# Colour_Sensor.net
KiCad netlist of a schematic drawn in EAGLE
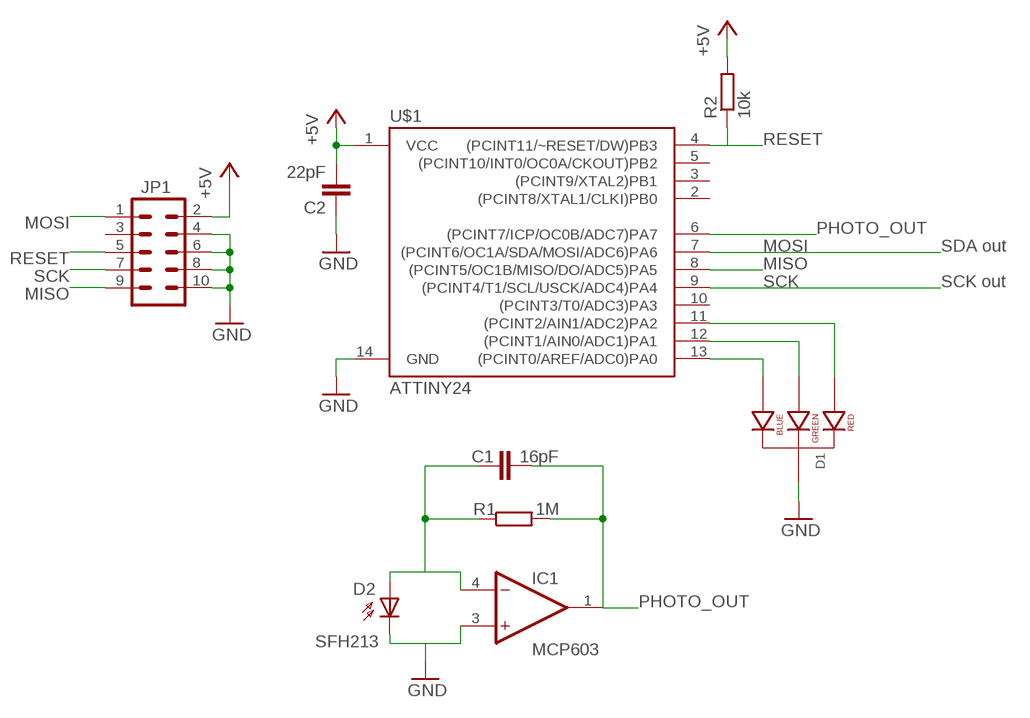
[diagram p0: schematic, sheet 1]

(export (version "E")
  (design (tool "Eeschema 10.0.6"))
  (components
    (comp (ref "C1")
      (value "16pF")
      (footprint "eagle-import:C025-024X044")
      (libsource (lib "eagle-import") (part "C-EU025-024X044"))
    )
    (comp (ref "C2")
      (value "22pF")
      (footprint "eagle-import:C025-024X044")
      (libsource (lib "eagle-import") (part "C-EU025-024X044"))
    )
    (comp (ref "D1")
      (value "LED-RGB-CC-THRUCLEAR")
      (footprint "eagle-import:LED-RGB-THRU")
      (libsource (lib "eagle-import") (part "LED-RGB-CC-THRUCLEAR"))
    )
    (comp (ref "D2")
      (value "SFH213")
      (footprint "eagle-import:BPW32")
      (libsource (lib "eagle-import") (part "BPW32"))
    )
    (comp (ref "IC1")
      (value "MCP603")
      (footprint "eagle-import:SOT23-5L")
      (fields (field (name "MPN") "MAX4105EUK+T"))
      (libsource (lib "eagle-import") (part "MAX4105EUK"))
    )
    (comp (ref "JP1")
      (value "M05X2SHD")
      (footprint "eagle-import:2X5-SHROUDED")
      (libsource (lib "eagle-import") (part "M05X2SHD"))
    )
    (comp (ref "R1")
      (value "1M")
      (footprint "eagle-import:0207_7")
      (libsource (lib "eagle-import") (part "R-EU_0207/7"))
    )
    (comp (ref "R2")
      (value "10k")
      (footprint "eagle-import:0207_7")
      (libsource (lib "eagle-import") (part "R-EU_0207/7"))
    )
    (comp (ref "U$1")
      (value "ATTINY24")
      (footprint "eagle-import:DIL14")
      (libsource (lib "eagle-import") (part "ATTINY84ATTINY84-20PU"))
    )
  )
  (nets
    (net (code "1") (name "+5V") (class "Default")
      (node (ref "C2") (pin "2") (pinfunction "2_2") (pintype "passive"))
      (node (ref "JP1") (pin "2") (pinfunction "2_2") (pintype "passive"))
      (node (ref "R2") (pin "2") (pinfunction "2_2") (pintype "passive"))
      (node (ref "U$1") (pin "1") (pinfunction "VCC_1") (pintype "bidirectional"))
    )
    (net (code "2") (name "/MISO") (class "Default")
      (node (ref "JP1") (pin "9") (pinfunction "9_9") (pintype "passive"))
      (node (ref "U$1") (pin "8") (pinfunction "(PCINT5/OC1B/MISO/DO/ADC5)PA5_8") (pintype "bidirectional"))
    )
    (net (code "3") (name "/MOSI") (class "Default")
      (node (ref "JP1") (pin "1") (pinfunction "1_1") (pintype "passive"))
      (node (ref "U$1") (pin "7") (pinfunction "(PCINT6/OC1A/SDA/MOSI/ADC6)PA6_7") (pintype "bidirectional"))
    )
    (net (code "4") (name "/PHOTO_OUT") (class "Default")
      (node (ref "C1") (pin "2") (pinfunction "2_2") (pintype "passive"))
      (node (ref "IC1") (pin "1") (pinfunction "OUT_1") (pintype "output"))
      (node (ref "R1") (pin "2") (pinfunction "2_2") (pintype "passive"))
      (node (ref "U$1") (pin "6") (pinfunction "(PCINT7/ICP/OC0B/ADC7)PA7_6") (pintype "bidirectional"))
    )
    (net (code "5") (name "/RESET") (class "Default")
      (node (ref "JP1") (pin "5") (pinfunction "5_5") (pintype "passive"))
      (node (ref "R2") (pin "1") (pinfunction "1_1") (pintype "passive"))
      (node (ref "U$1") (pin "4") (pinfunction "(PCINT11/~{RESET/DW})PB3_4") (pintype "bidirectional"))
    )
    (net (code "6") (name "/SCK") (class "Default")
      (node (ref "JP1") (pin "7") (pinfunction "7_7") (pintype "passive"))
      (node (ref "U$1") (pin "9") (pinfunction "(PCINT4/T1/SCL/USCK/ADC4)PA4_9") (pintype "bidirectional"))
    )
    (net (code "7") (name "GND") (class "Default")
      (node (ref "C2") (pin "1") (pinfunction "1_1") (pintype "passive"))
      (node (ref "D1") (pin "2") (pinfunction "CATHODE_2") (pintype "bidirectional"))
      (node (ref "D2") (pin "K") (pinfunction "C_K") (pintype "passive"))
      (node (ref "IC1") (pin "3") (pinfunction "+IN_3") (pintype "input"))
      (node (ref "JP1") (pin "10") (pinfunction "10_10") (pintype "passive"))
      (node (ref "JP1") (pin "4") (pinfunction "4_4") (pintype "passive"))
      (node (ref "JP1") (pin "6") (pinfunction "6_6") (pintype "passive"))
      (node (ref "JP1") (pin "8") (pinfunction "8_8") (pintype "passive"))
      (node (ref "U$1") (pin "14") (pinfunction "GND_14") (pintype "bidirectional"))
    )
    (net (code "8") (name "Net-(D1-BLUE_CATHODE)") (class "Default")
      (node (ref "D1") (pin "4") (pinfunction "BLUE_CATHODE_4") (pintype "bidirectional"))
      (node (ref "U$1") (pin "13") (pinfunction "(PCINT0/AREF/ADC0)PA0_13") (pintype "bidirectional"))
    )
    (net (code "9") (name "Net-(D1-GREEN_CATHODE)") (class "Default")
      (node (ref "D1") (pin "3") (pinfunction "GREEN_CATHODE_3") (pintype "bidirectional"))
      (node (ref "U$1") (pin "12") (pinfunction "(PCINT1/AIN0/ADC1)PA1_12") (pintype "bidirectional"))
    )
    (net (code "10") (name "Net-(D1-RED_CATHODE)") (class "Default")
      (node (ref "D1") (pin "1") (pinfunction "RED_CATHODE_1") (pintype "bidirectional"))
      (node (ref "U$1") (pin "11") (pinfunction "(PCINT2/AIN1/ADC2)PA2_11") (pintype "bidirectional"))
    )
    (net (code "11") (name "Net-(IC1A--IN)") (class "Default")
      (node (ref "C1") (pin "1") (pinfunction "1_1") (pintype "passive"))
      (node (ref "D2") (pin "A") (pinfunction "A_A") (pintype "passive"))
      (node (ref "IC1") (pin "4") (pinfunction "-IN_4") (pintype "input"))
      (node (ref "R1") (pin "1") (pinfunction "1_1") (pintype "passive"))
    )
    (net (code "12") (name "unconnected-(JP1-Pad3)") (class "Default")
      (node (ref "JP1") (pin "3") (pinfunction "3_3") (pintype "passive"))
    )
    (net (code "13") (name "unconnected-(U$1-(PCINT3{slash}T0{slash}ADC3)PA3-Pad10)") (class "Default")
      (node (ref "U$1") (pin "10") (pinfunction "(PCINT3/T0/ADC3)PA3_10") (pintype "bidirectional"))
    )
    (net (code "14") (name "unconnected-(U$1-(PCINT8{slash}XTAL1{slash}CLKI)PB0-Pad2)") (class "Default")
      (node (ref "U$1") (pin "2") (pinfunction "(PCINT8/XTAL1/CLKI)PB0_2") (pintype "bidirectional"))
    )
    (net (code "15") (name "unconnected-(U$1-(PCINT9{slash}XTAL2)PB1-Pad3)") (class "Default")
      (node (ref "U$1") (pin "3") (pinfunction "(PCINT9/XTAL2)PB1_3") (pintype "bidirectional"))
    )
    (net (code "16") (name "unconnected-(U$1-(PCINT10{slash}INT0{slash}OC0A{slash}CKOUT)PB2-Pad5)") (class "Default")
      (node (ref "U$1") (pin "5") (pinfunction "(PCINT10/INT0/OC0A/CKOUT)PB2_5") (pintype "bidirectional"))
    )
  )
)
